# BottomPCB.net
KiCad netlist of a schematic drawn in EAGLE
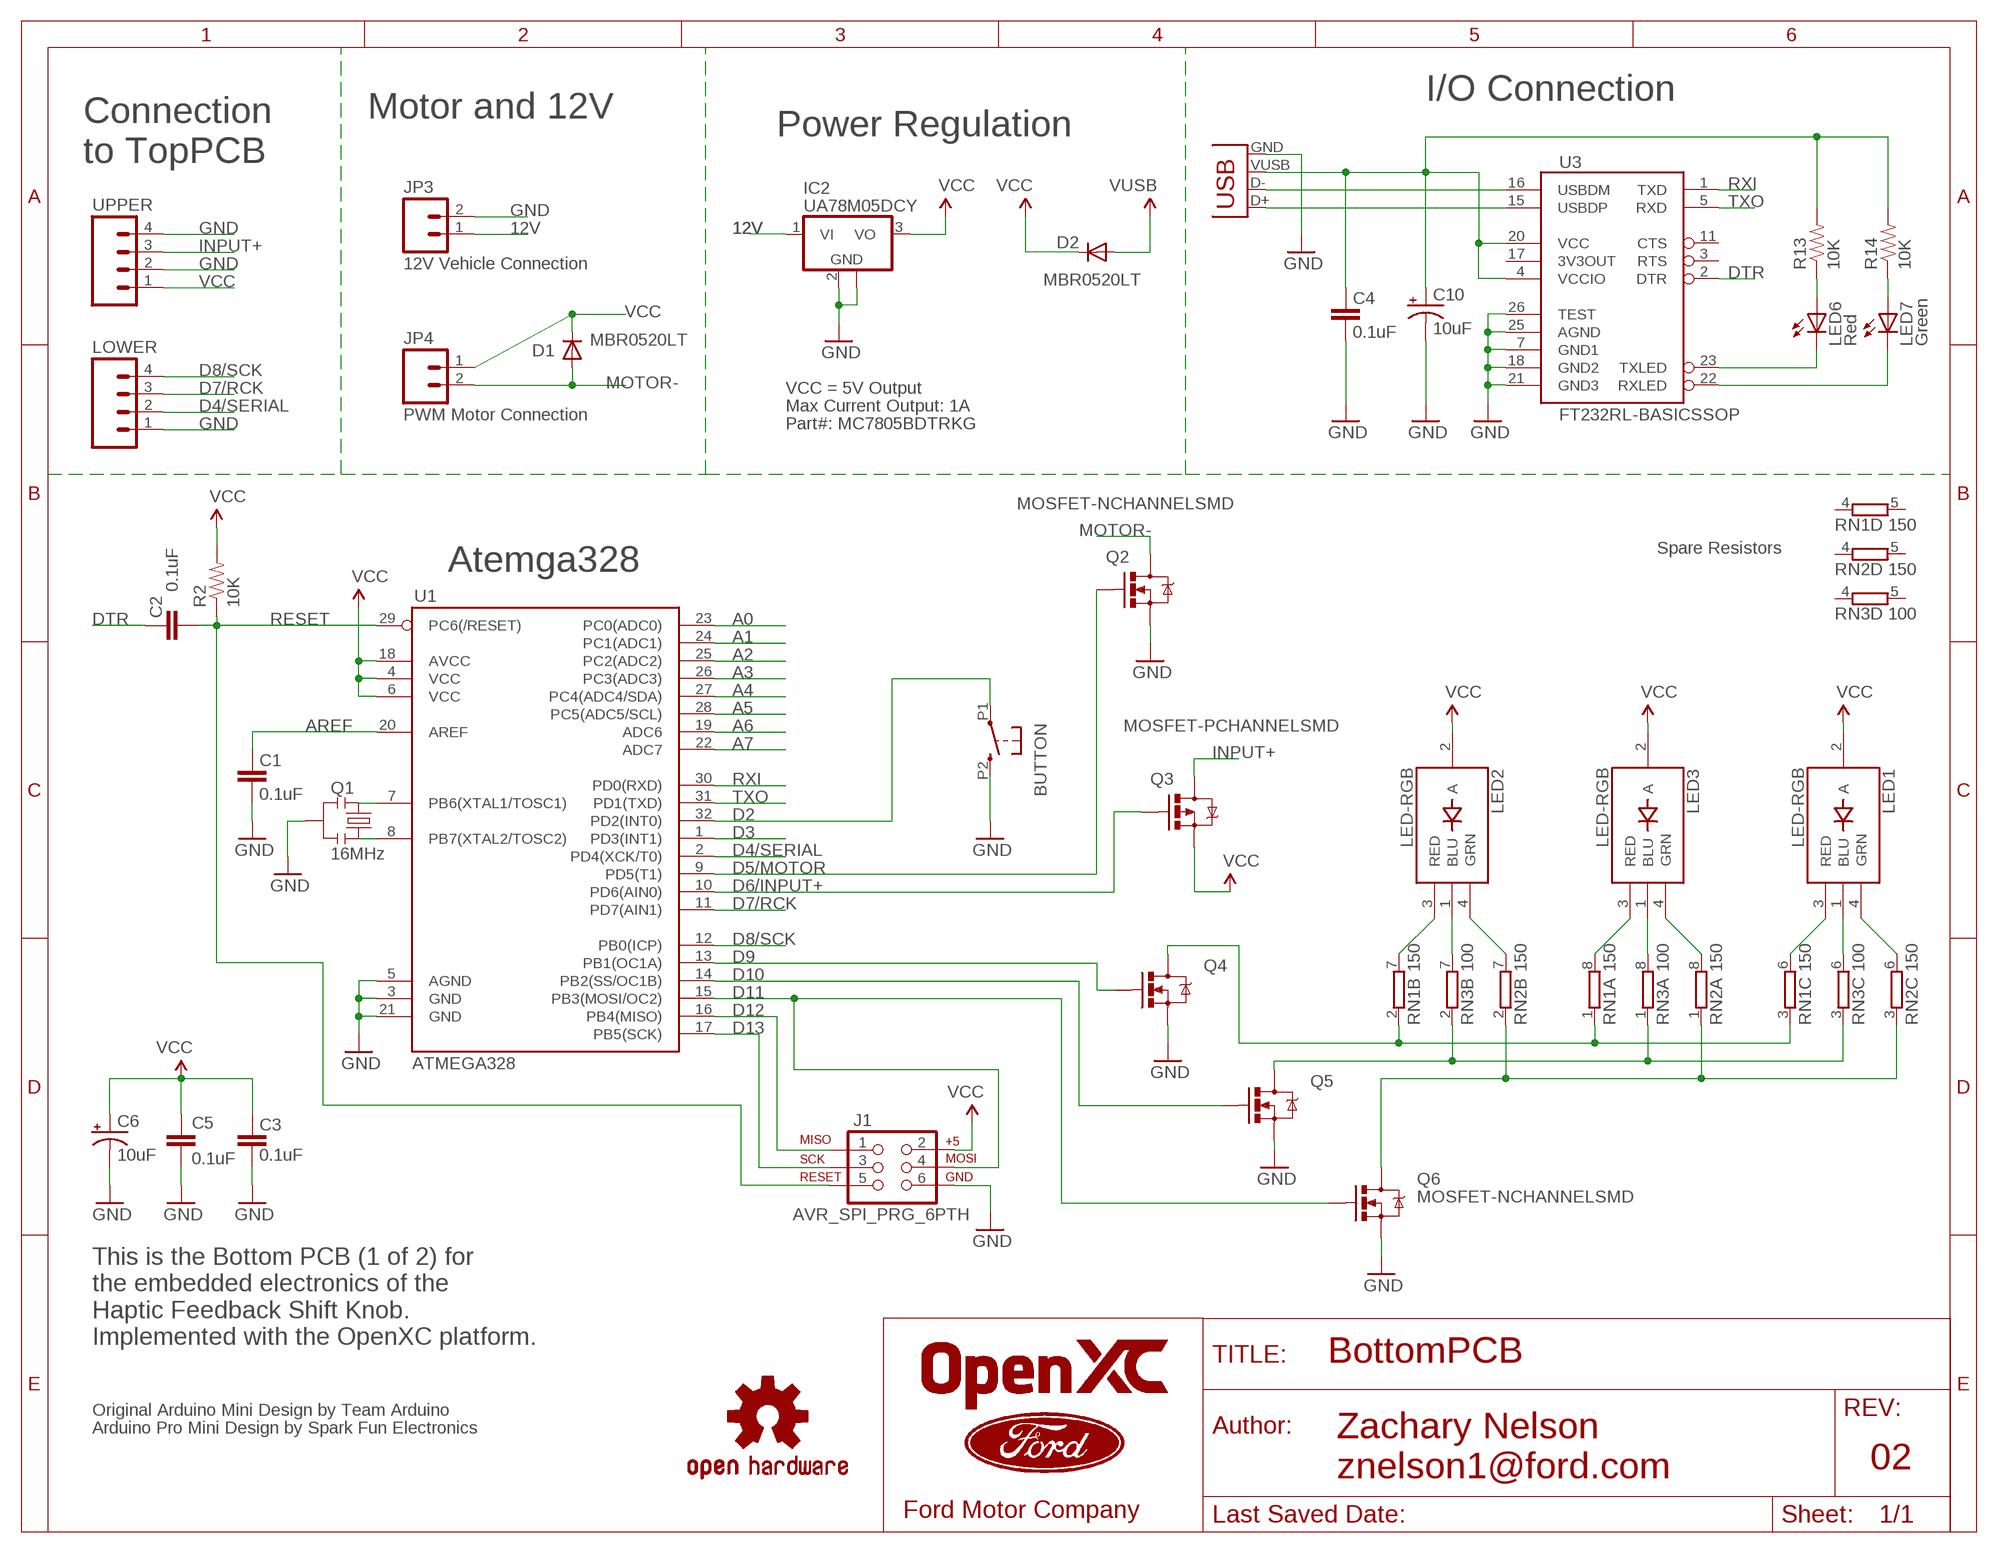
[diagram p0: schematic, sheet 1]

(export (version "E")
  (design (tool "Eeschema 10.0.6"))
  (components
    (comp (ref "BUTTON")
      (value "BUTTON_EDGE")
      (footprint "eagle-import:BUTTON_EDGE")
      (libsource (lib "eagle-import") (part "BUTTON_EDGE"))
    )
    (comp (ref "C1")
      (value "0.1uF")
      (footprint "eagle-import:0402-CAP")
      (libsource (lib "eagle-import") (part "CAP0402-CAP"))
    )
    (comp (ref "C2")
      (value "0.1uF")
      (footprint "eagle-import:0402-CAP")
      (libsource (lib "eagle-import") (part "CAP0402-CAP"))
    )
    (comp (ref "C3")
      (value "0.1uF")
      (footprint "eagle-import:0402-CAP")
      (libsource (lib "eagle-import") (part "CAP0402-CAP"))
    )
    (comp (ref "C4")
      (value "0.1uF")
      (footprint "eagle-import:0402-CAP")
      (libsource (lib "eagle-import") (part "CAP0402-CAP"))
    )
    (comp (ref "C5")
      (value "0.1uF")
      (footprint "eagle-import:0402-CAP")
      (libsource (lib "eagle-import") (part "CAP0402-CAP"))
    )
    (comp (ref "C6")
      (value "10uF")
      (footprint "eagle-import:EIA3216")
      (libsource (lib "eagle-import") (part "CAP_POL1206"))
    )
    (comp (ref "C10")
      (value "10uF")
      (footprint "eagle-import:EIA3216")
      (libsource (lib "eagle-import") (part "CAP_POL1206"))
    )
    (comp (ref "D1")
      (value "MBR0520LT")
      (footprint "eagle-import:SOD123")
      (libsource (lib "eagle-import") (part "MBR0520LT"))
    )
    (comp (ref "D2")
      (value "MBR0520LT")
      (footprint "eagle-import:SOD123")
      (libsource (lib "eagle-import") (part "MBR0520LT"))
    )
    (comp (ref "IC2")
      (value "UA78M05DCY")
      (footprint "eagle-import:SOT223")
      (libsource (lib "eagle-import") (part "UA78MDCY05"))
    )
    (comp (ref "J1")
      (value "AVR_SPI_PRG_6PTH")
      (footprint "eagle-import:2X3")
      (libsource (lib "eagle-import") (part "AVR_SPI_PRG_6PTH"))
    )
    (comp (ref "JP3")
      (value "12V Vehicle Connection")
      (footprint "eagle-import:1X02")
      (libsource (lib "eagle-import") (part "M02PTH"))
    )
    (comp (ref "JP4")
      (value "PWM Motor Connection")
      (footprint "eagle-import:JST-2-SMD")
      (libsource (lib "eagle-import") (part "M02-JST-2MM-SMT"))
    )
    (comp (ref "LED1")
      (value "LED-RGB")
      (footprint "eagle-import:LED-RGB_SMD-RIGHTANGLE")
      (libsource (lib "eagle-import") (part "LED-RGB"))
    )
    (comp (ref "LED2")
      (value "LED-RGB")
      (footprint "eagle-import:LED-RGB_SMD-RIGHTANGLE")
      (libsource (lib "eagle-import") (part "LED-RGB"))
    )
    (comp (ref "LED3")
      (value "LED-RGB")
      (footprint "eagle-import:LED-RGB_SMD-RIGHTANGLE")
      (libsource (lib "eagle-import") (part "LED-RGB"))
    )
    (comp (ref "LED6")
      (value "Red")
      (footprint "eagle-import:LED-0603")
      (libsource (lib "eagle-import") (part "LED0603"))
    )
    (comp (ref "LED7")
      (value "Green")
      (footprint "eagle-import:LED-0603")
      (libsource (lib "eagle-import") (part "LED0603"))
    )
    (comp (ref "LOWER")
      (value "M04PTH")
      (footprint "eagle-import:1X04")
      (libsource (lib "eagle-import") (part "M04PTH"))
    )
    (comp (ref "Q1")
      (value "16MHz")
      (footprint "eagle-import:RESONATOR-SMD")
      (libsource (lib "eagle-import") (part "RESONATORSMD"))
    )
    (comp (ref "Q2")
      (value "MOSFET-NCHANNELSMD")
      (footprint "eagle-import:SOT23-3")
      (libsource (lib "eagle-import") (part "MOSFET-NCHANNELSMD"))
    )
    (comp (ref "Q3")
      (value "MOSFET-PCHANNELSMD")
      (footprint "eagle-import:SOT23-3")
      (libsource (lib "eagle-import") (part "MOSFET-PCHANNELSMD"))
    )
    (comp (ref "Q4")
      (value "MOSFET-NCHANNELSMD")
      (footprint "eagle-import:SOT23-3")
      (libsource (lib "eagle-import") (part "MOSFET-NCHANNELSMD"))
    )
    (comp (ref "Q5")
      (value "MOSFET-NCHANNELSMD")
      (footprint "eagle-import:SOT23-3")
      (libsource (lib "eagle-import") (part "MOSFET-NCHANNELSMD"))
    )
    (comp (ref "Q6")
      (value "MOSFET-NCHANNELSMD")
      (footprint "eagle-import:SOT23-3")
      (libsource (lib "eagle-import") (part "MOSFET-NCHANNELSMD"))
    )
    (comp (ref "R2")
      (value "10K")
      (footprint "eagle-import:0402-RES")
      (libsource (lib "eagle-import") (part "RESISTOR0402-RES"))
    )
    (comp (ref "R13")
      (value "10K")
      (footprint "eagle-import:0402-RES")
      (libsource (lib "eagle-import") (part "RESISTOR0402-RES"))
    )
    (comp (ref "R14")
      (value "10K")
      (footprint "eagle-import:0402-RES")
      (libsource (lib "eagle-import") (part "RESISTOR0402-RES"))
    )
    (comp (ref "RN1")
      (value "150")
      (footprint "eagle-import:EXBS8V")
      (libsource (lib "eagle-import") (part "4R-NEXBS8V"))
    )
    (comp (ref "RN2")
      (value "150")
      (footprint "eagle-import:EXBS8V")
      (fields (field (name "OC_FARNELL") "unknown") (field (name "OC_NEWARK") "unknown"))
      (libsource (lib "eagle-import") (part "4R-NEXBS8V"))
    )
    (comp (ref "RN3")
      (value "100")
      (footprint "eagle-import:EXBS8V")
      (fields (field (name "OC_FARNELL") "unknown") (field (name "OC_NEWARK") "unknown"))
      (libsource (lib "eagle-import") (part "4R-NEXBS8V"))
    )
    (comp (ref "U$3")
      (value "OSHW-LOGOS")
      (footprint "eagle-import:OSHW-LOGO-S")
      (libsource (lib "eagle-import") (part "OSHW-LOGOS"))
    )
    (comp (ref "U1")
      (value "ATMEGA328")
      (footprint "eagle-import:TQFP32-08")
      (libsource (lib "eagle-import") (part "ATMEGA168"))
    )
    (comp (ref "U3")
      (value "FT232RL-BASICSSOP")
      (footprint "eagle-import:SSOP28DB")
      (libsource (lib "eagle-import") (part "FT232RL-BASICSSOP"))
    )
    (comp (ref "U6")
      (value "USB-MINI-B_VERTICAL")
      (footprint "eagle-import:USB-MINI-B_VERTICAL")
      (libsource (lib "eagle-import") (part "USB-MINI-B_VERTICAL"))
    )
    (comp (ref "UPPER")
      (value "M04PTH")
      (footprint "eagle-import:1X04")
      (libsource (lib "eagle-import") (part "M04PTH"))
    )
  )
  (nets
    (net (code "1") (name "/12V") (class "Default")
      (node (ref "IC2") (pin "1") (pinfunction "VI_1") (pintype "input"))
      (node (ref "JP3") (pin "1") (pinfunction "1_1") (pintype "passive"))
    )
    (net (code "2") (name "/A0") (class "Default")
      (node (ref "U1") (pin "23") (pinfunction "PC0(ADC0)_23") (pintype "bidirectional"))
    )
    (net (code "3") (name "/A1") (class "Default")
      (node (ref "U1") (pin "24") (pinfunction "PC1(ADC1)_24") (pintype "bidirectional"))
    )
    (net (code "4") (name "/A2") (class "Default")
      (node (ref "U1") (pin "25") (pinfunction "PC2(ADC2)_25") (pintype "bidirectional"))
    )
    (net (code "5") (name "/A3") (class "Default")
      (node (ref "U1") (pin "26") (pinfunction "PC3(ADC3)_26") (pintype "bidirectional"))
    )
    (net (code "6") (name "/A4") (class "Default")
      (node (ref "U1") (pin "27") (pinfunction "PC4(ADC4/SDA)_27") (pintype "bidirectional"))
    )
    (net (code "7") (name "/A5") (class "Default")
      (node (ref "U1") (pin "28") (pinfunction "PC5(ADC5/SCL)_28") (pintype "bidirectional"))
    )
    (net (code "8") (name "/A6") (class "Default")
      (node (ref "U1") (pin "19") (pinfunction "ADC6_19") (pintype "bidirectional"))
    )
    (net (code "9") (name "/A7") (class "Default")
      (node (ref "U1") (pin "22") (pinfunction "ADC7_22") (pintype "bidirectional"))
    )
    (net (code "10") (name "/AREF") (class "Default")
      (node (ref "C1") (pin "2") (pinfunction "2_2") (pintype "passive"))
      (node (ref "U1") (pin "20") (pinfunction "AREF_20") (pintype "bidirectional"))
    )
    (net (code "11") (name "/D2") (class "Default")
      (node (ref "BUTTON") (pin "P1") (pinfunction "1_P1") (pintype "passive"))
      (node (ref "U1") (pin "32") (pinfunction "PD2(INT0)_32") (pintype "bidirectional"))
    )
    (net (code "12") (name "/D3") (class "Default")
      (node (ref "U1") (pin "1") (pinfunction "PD3(INT1)_1") (pintype "bidirectional"))
    )
    (net (code "13") (name "/D4{slash}SERIAL") (class "Default")
      (node (ref "LOWER") (pin "2") (pinfunction "2_2") (pintype "passive"))
      (node (ref "U1") (pin "2") (pinfunction "PD4(XCK/T0)_2") (pintype "bidirectional"))
    )
    (net (code "14") (name "/D5{slash}MOTOR") (class "Default")
      (node (ref "Q2") (pin "1") (pinfunction "G_1") (pintype "passive"))
      (node (ref "U1") (pin "9") (pinfunction "PD5(T1)_9") (pintype "bidirectional"))
    )
    (net (code "15") (name "/D6{slash}INPUT+") (class "Default")
      (node (ref "Q3") (pin "1") (pinfunction "G_1") (pintype "passive"))
      (node (ref "U1") (pin "10") (pinfunction "PD6(AIN0)_10") (pintype "bidirectional"))
    )
    (net (code "16") (name "/D7{slash}RCK") (class "Default")
      (node (ref "LOWER") (pin "3") (pinfunction "3_3") (pintype "passive"))
      (node (ref "U1") (pin "11") (pinfunction "PD7(AIN1)_11") (pintype "bidirectional"))
    )
    (net (code "17") (name "/D8{slash}SCK") (class "Default")
      (node (ref "LOWER") (pin "4") (pinfunction "4_4") (pintype "passive"))
      (node (ref "U1") (pin "12") (pinfunction "PB0(ICP)_12") (pintype "bidirectional"))
    )
    (net (code "18") (name "/D9") (class "Default")
      (node (ref "Q4") (pin "3") (pinfunction "D_3") (pintype "passive"))
      (node (ref "RN1") (pin "1") (pinfunction "1_1") (pintype "passive"))
      (node (ref "RN1") (pin "2") (pinfunction "1_2") (pintype "passive"))
      (node (ref "RN1") (pin "3") (pinfunction "1_3") (pintype "passive"))
    )
    (net (code "19") (name "/D10") (class "Default")
      (node (ref "Q5") (pin "3") (pinfunction "D_3") (pintype "passive"))
      (node (ref "RN3") (pin "1") (pinfunction "1_1") (pintype "passive"))
      (node (ref "RN3") (pin "2") (pinfunction "1_2") (pintype "passive"))
      (node (ref "RN3") (pin "3") (pinfunction "1_3") (pintype "passive"))
    )
    (net (code "20") (name "/D11") (class "Default")
      (node (ref "Q6") (pin "3") (pinfunction "D_3") (pintype "passive"))
      (node (ref "RN2") (pin "1") (pinfunction "1_1") (pintype "passive"))
      (node (ref "RN2") (pin "2") (pinfunction "1_2") (pintype "passive"))
      (node (ref "RN2") (pin "3") (pinfunction "1_3") (pintype "passive"))
    )
    (net (code "21") (name "/D12") (class "Default")
      (node (ref "J1") (pin "1") (pinfunction "1_1") (pintype "passive"))
      (node (ref "U1") (pin "16") (pinfunction "PB4(MISO)_16") (pintype "bidirectional"))
    )
    (net (code "22") (name "/D13") (class "Default")
      (node (ref "J1") (pin "3") (pinfunction "3_3") (pintype "passive"))
      (node (ref "U1") (pin "17") (pinfunction "PB5(SCK)_17") (pintype "bidirectional"))
    )
    (net (code "23") (name "/DTR") (class "Default")
      (node (ref "C2") (pin "2") (pinfunction "2_2") (pintype "passive"))
      (node (ref "U3") (pin "2") (pinfunction "DTR_2") (pintype "bidirectional"))
    )
    (net (code "24") (name "/INPUT+") (class "Default")
      (node (ref "Q3") (pin "3") (pinfunction "D_3") (pintype "passive"))
      (node (ref "UPPER") (pin "3") (pinfunction "3_3") (pintype "passive"))
    )
    (net (code "25") (name "/MOTOR-") (class "Default")
      (node (ref "D1") (pin "A") (pinfunction "A_A") (pintype "passive"))
      (node (ref "JP4") (pin "2") (pinfunction "1_2") (pintype "passive"))
      (node (ref "Q2") (pin "3") (pinfunction "D_3") (pintype "passive"))
    )
    (net (code "26") (name "/RESET") (class "Default")
      (node (ref "C2") (pin "1") (pinfunction "1_1") (pintype "passive"))
      (node (ref "J1") (pin "5") (pinfunction "5_5") (pintype "passive"))
      (node (ref "R2") (pin "1") (pinfunction "1_1") (pintype "passive"))
      (node (ref "U1") (pin "29") (pinfunction "PC6(/RESET)_29") (pintype "bidirectional"))
    )
    (net (code "27") (name "/RXI") (class "Default")
      (node (ref "U1") (pin "30") (pinfunction "PD0(RXD)_30") (pintype "bidirectional"))
      (node (ref "U3") (pin "1") (pinfunction "TXD_1") (pintype "output"))
    )
    (net (code "28") (name "/TXO") (class "Default")
      (node (ref "U1") (pin "31") (pinfunction "PD1(TXD)_31") (pintype "bidirectional"))
      (node (ref "U3") (pin "5") (pinfunction "RXD_5") (pintype "input"))
    )
    (net (code "29") (name "GND") (class "Default")
      (node (ref "BUTTON") (pin "P2") (pinfunction "2_P2") (pintype "passive"))
      (node (ref "C1") (pin "1") (pinfunction "1_1") (pintype "passive"))
      (node (ref "C10") (pin "C") (pinfunction "-_C") (pintype "passive"))
      (node (ref "C3") (pin "1") (pinfunction "1_1") (pintype "passive"))
      (node (ref "C4") (pin "1") (pinfunction "1_1") (pintype "passive"))
      (node (ref "C5") (pin "2") (pinfunction "2_2") (pintype "passive"))
      (node (ref "C6") (pin "C") (pinfunction "-_C") (pintype "passive"))
      (node (ref "IC2") (pin "2") (pinfunction "GND_2") (pintype "passive"))
      (node (ref "IC2") (pin "4") (pinfunction "GND_4") (pintype "passive"))
      (node (ref "J1") (pin "6") (pinfunction "6_6") (pintype "passive"))
      (node (ref "JP3") (pin "2") (pinfunction "2_2") (pintype "passive"))
      (node (ref "LOWER") (pin "1") (pinfunction "1_1") (pintype "passive"))
      (node (ref "Q1") (pin "2") (pinfunction "2_2") (pintype "passive"))
      (node (ref "Q2") (pin "2") (pinfunction "S_2") (pintype "passive"))
      (node (ref "Q4") (pin "2") (pinfunction "S_2") (pintype "passive"))
      (node (ref "Q5") (pin "2") (pinfunction "S_2") (pintype "passive"))
      (node (ref "Q6") (pin "2") (pinfunction "S_2") (pintype "passive"))
      (node (ref "U1") (pin "21") (pinfunction "GND_21") (pintype "bidirectional"))
      (node (ref "U1") (pin "3") (pinfunction "GND_3") (pintype "bidirectional"))
      (node (ref "U1") (pin "5") (pinfunction "AGND_5") (pintype "bidirectional"))
      (node (ref "U3") (pin "18") (pinfunction "GND2_18") (pintype "power_in"))
      (node (ref "U3") (pin "21") (pinfunction "GND3_21") (pintype "power_in"))
      (node (ref "U3") (pin "25") (pinfunction "AGND_25") (pintype "power_in"))
      (node (ref "U3") (pin "26") (pinfunction "TEST_26") (pintype "input"))
      (node (ref "U3") (pin "7") (pinfunction "GND1_7") (pintype "power_in"))
      (node (ref "U6") (pin "GND") (pinfunction "GND_GND") (pintype "bidirectional"))
      (node (ref "UPPER") (pin "2") (pinfunction "2_2") (pintype "passive"))
      (node (ref "UPPER") (pin "4") (pinfunction "4_4") (pintype "passive"))
    )
    (net (code "30") (name "Net-(LED1-BLU)") (class "Default")
      (node (ref "LED1") (pin "1") (pinfunction "BLU_1") (pintype "bidirectional"))
      (node (ref "RN3") (pin "6") (pinfunction "2_6") (pintype "passive"))
    )
    (net (code "31") (name "Net-(LED1-GRN)") (class "Default")
      (node (ref "LED1") (pin "4") (pinfunction "GRN_4") (pintype "bidirectional"))
      (node (ref "RN2") (pin "6") (pinfunction "2_6") (pintype "passive"))
    )
    (net (code "32") (name "Net-(LED1-RED)") (class "Default")
      (node (ref "LED1") (pin "3") (pinfunction "RED_3") (pintype "bidirectional"))
      (node (ref "RN1") (pin "6") (pinfunction "2_6") (pintype "passive"))
    )
    (net (code "33") (name "Net-(LED2-BLU)") (class "Default")
      (node (ref "LED2") (pin "1") (pinfunction "BLU_1") (pintype "bidirectional"))
      (node (ref "RN3") (pin "7") (pinfunction "2_7") (pintype "passive"))
    )
    (net (code "34") (name "Net-(LED2-GRN)") (class "Default")
      (node (ref "LED2") (pin "4") (pinfunction "GRN_4") (pintype "bidirectional"))
      (node (ref "RN2") (pin "7") (pinfunction "2_7") (pintype "passive"))
    )
    (net (code "35") (name "Net-(LED2-RED)") (class "Default")
      (node (ref "LED2") (pin "3") (pinfunction "RED_3") (pintype "bidirectional"))
      (node (ref "RN1") (pin "7") (pinfunction "2_7") (pintype "passive"))
    )
    (net (code "36") (name "Net-(LED3-BLU)") (class "Default")
      (node (ref "LED3") (pin "1") (pinfunction "BLU_1") (pintype "bidirectional"))
      (node (ref "RN3") (pin "8") (pinfunction "2_8") (pintype "passive"))
    )
    (net (code "37") (name "Net-(LED3-GRN)") (class "Default")
      (node (ref "LED3") (pin "4") (pinfunction "GRN_4") (pintype "bidirectional"))
      (node (ref "RN2") (pin "8") (pinfunction "2_8") (pintype "passive"))
    )
    (net (code "38") (name "Net-(LED3-RED)") (class "Default")
      (node (ref "LED3") (pin "3") (pinfunction "RED_3") (pintype "bidirectional"))
      (node (ref "RN1") (pin "8") (pinfunction "2_8") (pintype "passive"))
    )
    (net (code "39") (name "Net-(LED6-PadA)") (class "Default")
      (node (ref "LED6") (pin "A") (pinfunction "A_A") (pintype "passive"))
      (node (ref "R13") (pin "1") (pinfunction "1_1") (pintype "passive"))
    )
    (net (code "40") (name "Net-(LED7-PadA)") (class "Default")
      (node (ref "LED7") (pin "A") (pinfunction "A_A") (pintype "passive"))
      (node (ref "R14") (pin "1") (pinfunction "1_1") (pintype "passive"))
    )
    (net (code "41") (name "Net-(Q4-G)") (class "Default")
      (node (ref "Q4") (pin "1") (pinfunction "G_1") (pintype "passive"))
      (node (ref "U1") (pin "13") (pinfunction "PB1(OC1A)_13") (pintype "bidirectional"))
    )
    (net (code "42") (name "Net-(Q5-G)") (class "Default")
      (node (ref "Q5") (pin "1") (pinfunction "G_1") (pintype "passive"))
      (node (ref "U1") (pin "14") (pinfunction "PB2(SS/OC1B)_14") (pintype "bidirectional"))
    )
    (net (code "43") (name "Net-(Q6-G)") (class "Default")
      (node (ref "J1") (pin "4") (pinfunction "4_4") (pintype "passive"))
      (node (ref "Q6") (pin "1") (pinfunction "G_1") (pintype "passive"))
      (node (ref "U1") (pin "15") (pinfunction "PB3(MOSI/OC2)_15") (pintype "bidirectional"))
    )
    (net (code "44") (name "Net-(U1-PB6(XTAL1{slash}TOSC1))") (class "Default")
      (node (ref "Q1") (pin "3") (pinfunction "3_3") (pintype "passive"))
      (node (ref "U1") (pin "7") (pinfunction "PB6(XTAL1/TOSC1)_7") (pintype "bidirectional"))
    )
    (net (code "45") (name "Net-(U1-PB7(XTAL2{slash}TOSC2))") (class "Default")
      (node (ref "Q1") (pin "1") (pinfunction "1_1") (pintype "passive"))
      (node (ref "U1") (pin "8") (pinfunction "PB7(XTAL2/TOSC2)_8") (pintype "bidirectional"))
    )
    (net (code "46") (name "Net-(U3-RXLED)") (class "Default")
      (node (ref "LED7") (pin "C") (pinfunction "C_C") (pintype "passive"))
      (node (ref "U3") (pin "22") (pinfunction "RXLED_22") (pintype "bidirectional"))
    )
    (net (code "47") (name "Net-(U3-TXLED)") (class "Default")
      (node (ref "LED6") (pin "C") (pinfunction "C_C") (pintype "passive"))
      (node (ref "U3") (pin "23") (pinfunction "TXLED_23") (pintype "bidirectional"))
    )
    (net (code "48") (name "Net-(U3-USBDM)") (class "Default")
      (node (ref "U3") (pin "16") (pinfunction "USBDM_16") (pintype "bidirectional"))
      (node (ref "U6") (pin "D-") (pinfunction "D-_D-") (pintype "bidirectional"))
    )
    (net (code "49") (name "Net-(U3-USBDP)") (class "Default")
      (node (ref "U3") (pin "15") (pinfunction "USBDP_15") (pintype "bidirectional"))
      (node (ref "U6") (pin "D+") (pinfunction "D+_D+") (pintype "bidirectional"))
    )
    (net (code "50") (name "VCC") (class "Default")
      (node (ref "C3") (pin "2") (pinfunction "2_2") (pintype "passive"))
      (node (ref "C5") (pin "1") (pinfunction "1_1") (pintype "passive"))
      (node (ref "C6") (pin "A") (pinfunction "+_A") (pintype "passive"))
      (node (ref "D1") (pin "C") (pinfunction "C_C") (pintype "passive"))
      (node (ref "D2") (pin "C") (pinfunction "C_C") (pintype "passive"))
      (node (ref "IC2") (pin "3") (pinfunction "VO_3") (pintype "passive"))
      (node (ref "J1") (pin "2") (pinfunction "2_2") (pintype "passive"))
      (node (ref "JP4") (pin "1") (pinfunction "2_1") (pintype "passive"))
      (node (ref "LED1") (pin "2") (pinfunction "A_2") (pintype "bidirectional"))
      (node (ref "LED2") (pin "2") (pinfunction "A_2") (pintype "bidirectional"))
      (node (ref "LED3") (pin "2") (pinfunction "A_2") (pintype "bidirectional"))
      (node (ref "Q3") (pin "2") (pinfunction "S_2") (pintype "passive"))
      (node (ref "R2") (pin "2") (pinfunction "2_2") (pintype "passive"))
      (node (ref "U1") (pin "18") (pinfunction "AVCC_18") (pintype "bidirectional"))
      (node (ref "U1") (pin "4") (pinfunction "VCC_4") (pintype "bidirectional"))
      (node (ref "U1") (pin "6") (pinfunction "VCC_6") (pintype "bidirectional"))
      (node (ref "UPPER") (pin "1") (pinfunction "1_1") (pintype "passive"))
    )
    (net (code "51") (name "VUSB") (class "Default")
      (node (ref "C10") (pin "A") (pinfunction "+_A") (pintype "passive"))
      (node (ref "C4") (pin "2") (pinfunction "2_2") (pintype "passive"))
      (node (ref "D2") (pin "A") (pinfunction "A_A") (pintype "passive"))
      (node (ref "R13") (pin "2") (pinfunction "2_2") (pintype "passive"))
      (node (ref "R14") (pin "2") (pinfunction "2_2") (pintype "passive"))
      (node (ref "U3") (pin "20") (pinfunction "VCC_20") (pintype "power_in"))
      (node (ref "U3") (pin "4") (pinfunction "VCCIO_4") (pintype "power_in"))
      (node (ref "U6") (pin "VUSB") (pinfunction "VBUS_VUSB") (pintype "bidirectional"))
    )
    (net (code "52") (name "unconnected-(RN1D-1-Pad4)") (class "Default")
      (node (ref "RN1") (pin "4") (pinfunction "1_4") (pintype "passive"))
    )
    (net (code "53") (name "unconnected-(RN1D-2-Pad5)") (class "Default")
      (node (ref "RN1") (pin "5") (pinfunction "2_5") (pintype "passive"))
    )
    (net (code "54") (name "unconnected-(RN2D-1-Pad4)") (class "Default")
      (node (ref "RN2") (pin "4") (pinfunction "1_4") (pintype "passive"))
    )
    (net (code "55") (name "unconnected-(RN2D-2-Pad5)") (class "Default")
      (node (ref "RN2") (pin "5") (pinfunction "2_5") (pintype "passive"))
    )
    (net (code "56") (name "unconnected-(RN3D-1-Pad4)") (class "Default")
      (node (ref "RN3") (pin "4") (pinfunction "1_4") (pintype "passive"))
    )
    (net (code "57") (name "unconnected-(RN3D-2-Pad5)") (class "Default")
      (node (ref "RN3") (pin "5") (pinfunction "2_5") (pintype "passive"))
    )
    (net (code "58") (name "unconnected-(U3-3V3OUT-Pad17)") (class "Default")
      (node (ref "U3") (pin "17") (pinfunction "3V3OUT_17") (pintype "output"))
    )
    (net (code "59") (name "unconnected-(U3-CTS-Pad11)") (class "Default")
      (node (ref "U3") (pin "11") (pinfunction "CTS_11") (pintype "bidirectional"))
    )
    (net (code "60") (name "unconnected-(U3-RTS-Pad3)") (class "Default")
      (node (ref "U3") (pin "3") (pinfunction "RTS_3") (pintype "bidirectional"))
    )
  )
)
